# RC-ESC_2020-12-18_19-57-09.net
KiCad netlist of a schematic drawn in EasyEDA
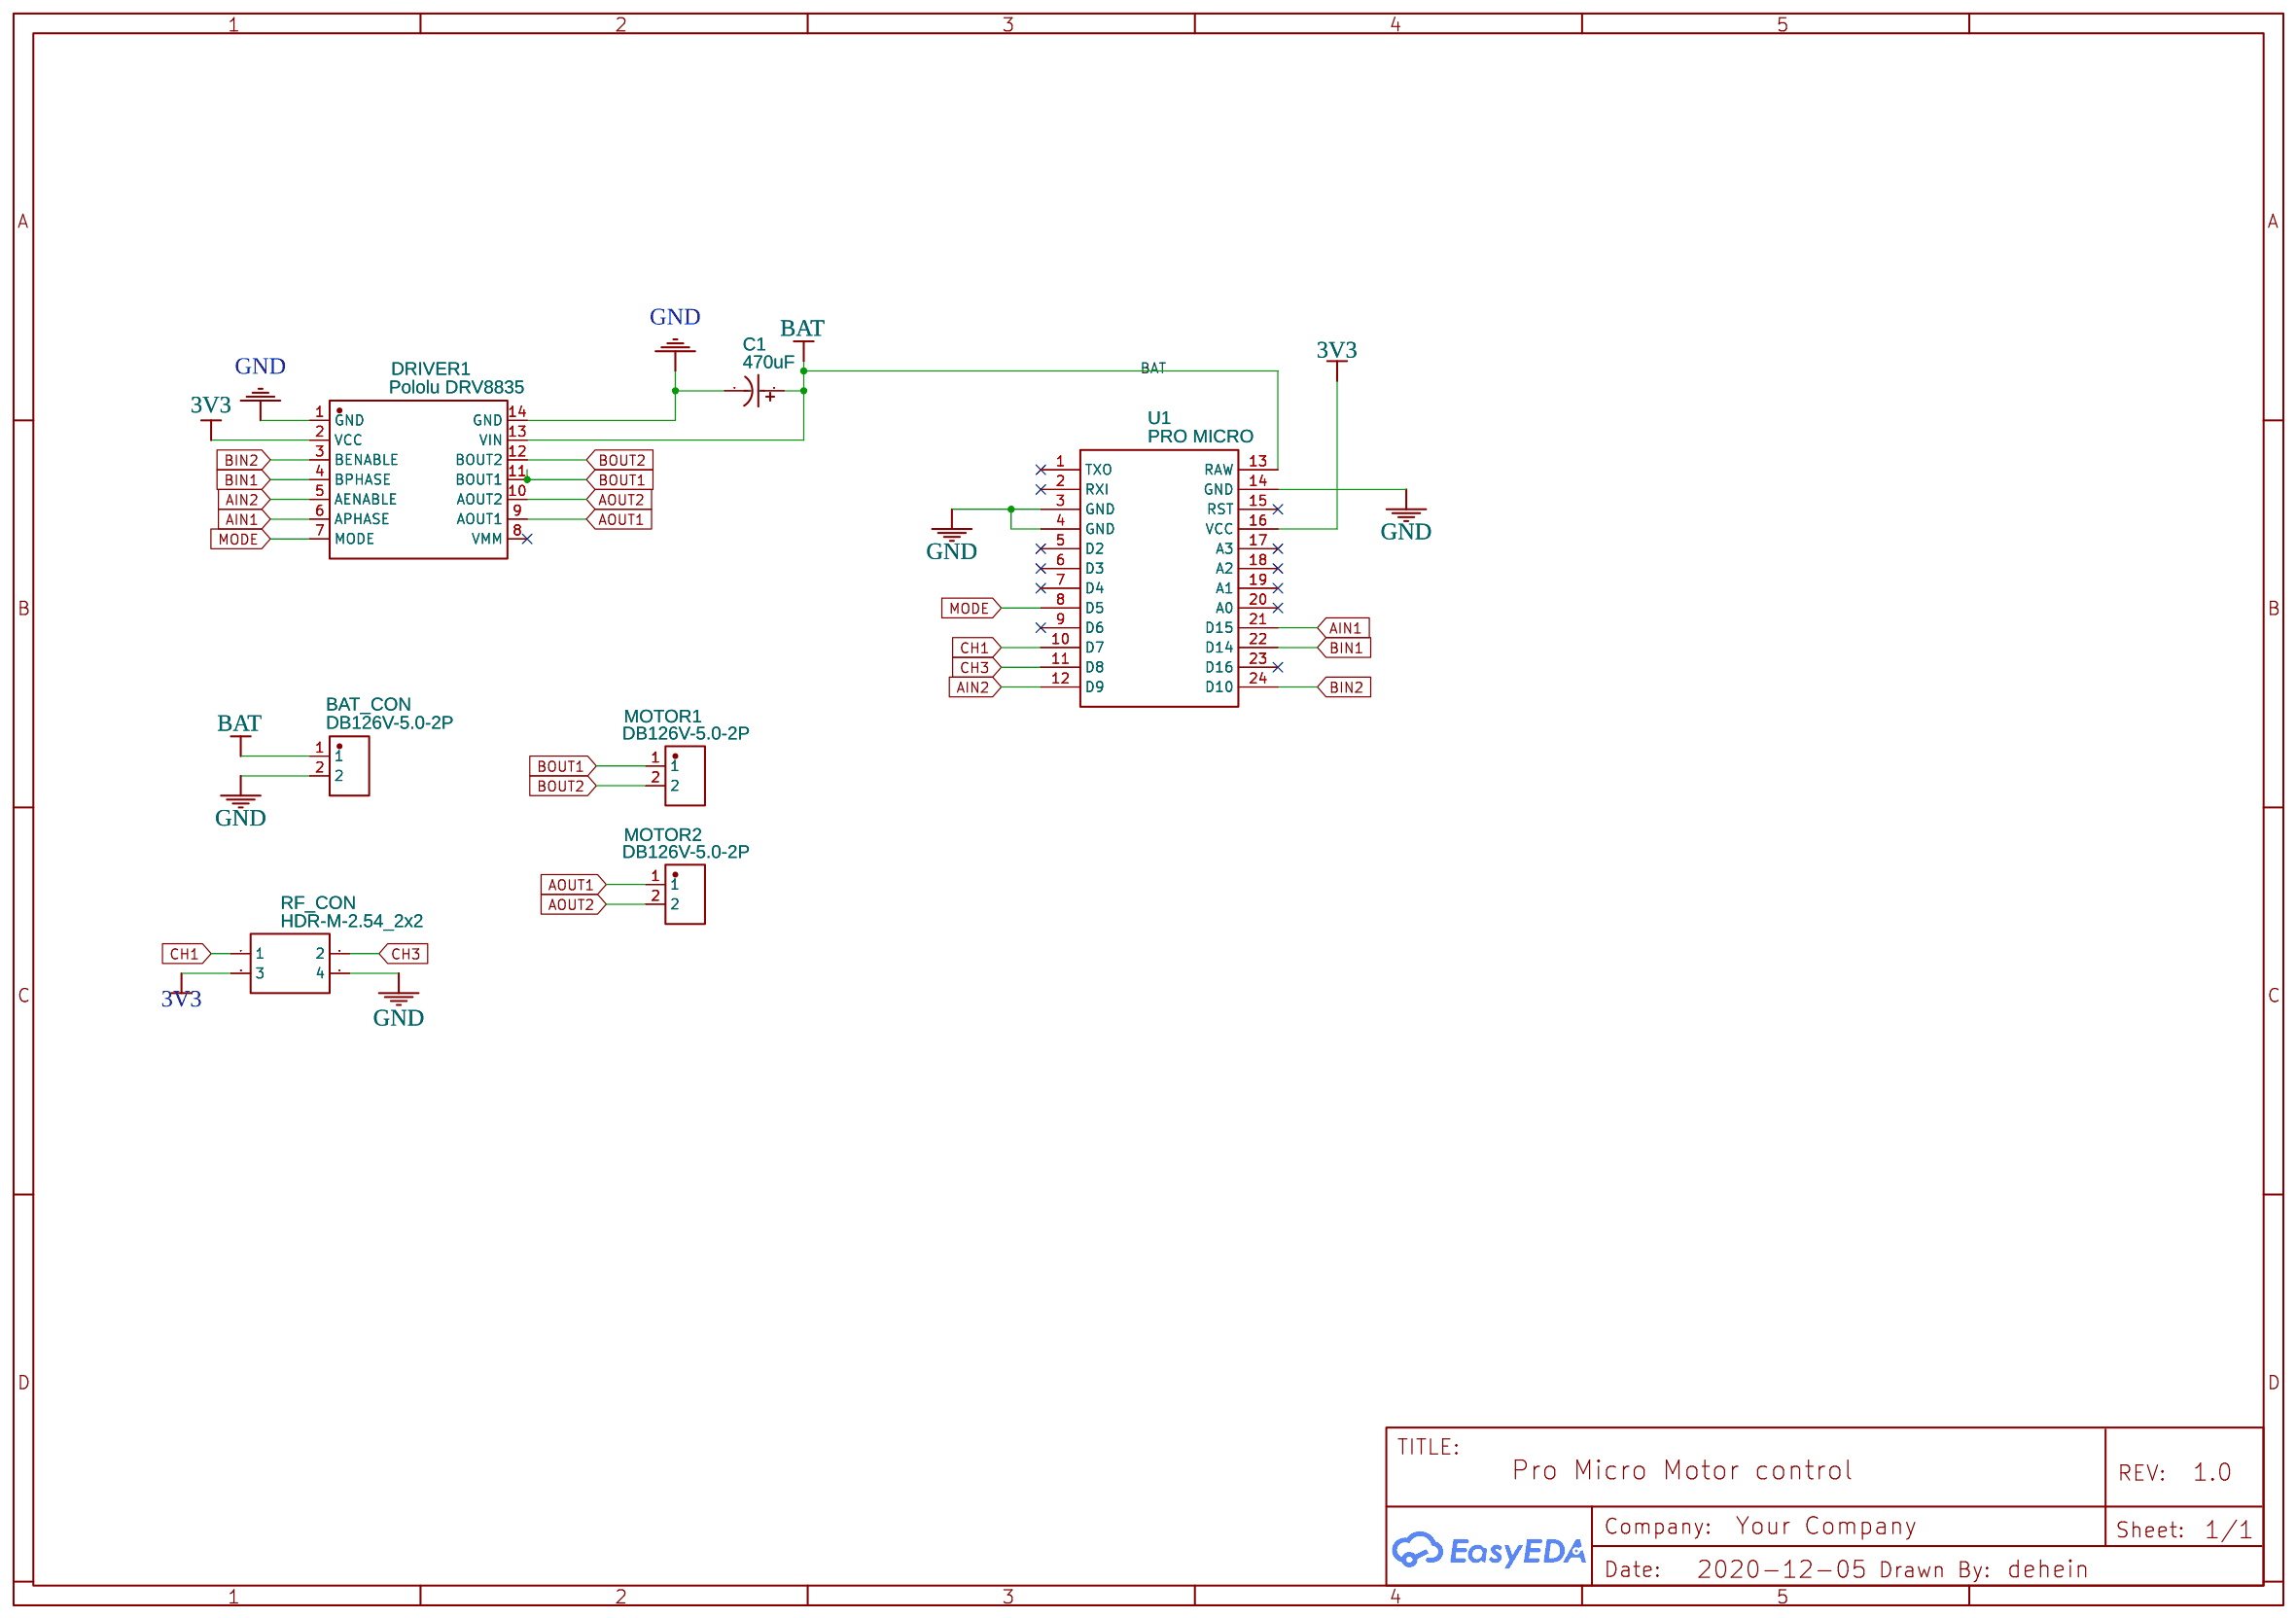
[diagram p0: schematic sheet]

(export (version "E")
  (design (tool "Eeschema 10.0.6"))
  (components
    (comp (ref "BAT_CON")
      (value "DB126V-5.0-2P")
      (fields (field (name "BOM_Supplier Part") "C395849"))
      (libsource (lib "") (part "DB126V-5.0-2P"))
    )
    (comp (ref "C1")
      (value "470uF")
      (fields
        (field (name "BOM_Manufacturer Part") "470uF 25V 8*12Black high frequency")
        (field (name "BOM_Supplier Part") "C44602")
      )
      (libsource (lib "") (part "470uF 25V 8*12Black high frequency"))
    )
    (comp (ref "DRIVER1")
      (value "Pololu DRV8835")
      (fields (field (name "BOM_Manufacturer Part") "2135"))
      (libsource (lib "") (part "Pololu DRV8835"))
    )
    (comp (ref "MOTOR1")
      (value "DB126V-5.0-2P")
      (fields (field (name "BOM_Supplier Part") "C395849"))
      (libsource (lib "") (part "DB126V-5.0-2P_1"))
    )
    (comp (ref "MOTOR2")
      (value "DB126V-5.0-2P")
      (fields (field (name "BOM_Supplier Part") "C395849"))
      (libsource (lib "") (part "DB126V-5.0-2P_1"))
    )
    (comp (ref "RF_CON")
      (value "HDR-M-2.54_2x2")
      (fields
        (field (name "BOM_Manufacturer Part") "Double Rows2.54mm2*2pHeaders  Pins")
        (field (name "BOM_Supplier Part") "C66690")
      )
      (libsource (lib "") (part "HDR-M-2.54_2x2"))
    )
    (comp (ref "U1") (value "PRO MICRO") (libsource (lib "") (part "PRO MICRO")))
  )
  (nets
    (net (code "1") (name "3V3") (class "Default")
      (node (ref "DRIVER1") (pin "2") (pinfunction "VCC_2") (pintype "unspecified"))
      (node (ref "RF_CON") (pin "3") (pinfunction "3_3") (pintype "input"))
      (node (ref "U1") (pin "16") (pinfunction "VCC_16") (pintype "unspecified"))
    )
    (net (code "2") (name "AIN1") (class "Default")
      (node (ref "DRIVER1") (pin "6") (pinfunction "APHASE_6") (pintype "unspecified"))
      (node (ref "U1") (pin "21") (pinfunction "D15_21") (pintype "unspecified"))
    )
    (net (code "3") (name "AIN2") (class "Default")
      (node (ref "DRIVER1") (pin "5") (pinfunction "AENABLE_5") (pintype "unspecified"))
      (node (ref "U1") (pin "12") (pinfunction "D9_12") (pintype "unspecified"))
    )
    (net (code "4") (name "AOUT1") (class "Default")
      (node (ref "DRIVER1") (pin "9") (pinfunction "AOUT1_9") (pintype "unspecified"))
      (node (ref "MOTOR2") (pin "1") (pinfunction "1_1") (pintype "unspecified"))
    )
    (net (code "5") (name "AOUT2") (class "Default")
      (node (ref "DRIVER1") (pin "10") (pinfunction "AOUT2_10") (pintype "unspecified"))
      (node (ref "MOTOR2") (pin "2") (pinfunction "2_2") (pintype "unspecified"))
    )
    (net (code "6") (name "BAT") (class "Default")
      (node (ref "BAT_CON") (pin "1") (pinfunction "1_1") (pintype "unspecified"))
      (node (ref "C1") (pin "1") (pinfunction "1_1") (pintype "input"))
      (node (ref "DRIVER1") (pin "13") (pinfunction "VIN_13") (pintype "unspecified"))
      (node (ref "U1") (pin "13") (pinfunction "RAW_13") (pintype "unspecified"))
    )
    (net (code "7") (name "BIN1") (class "Default")
      (node (ref "DRIVER1") (pin "4") (pinfunction "BPHASE_4") (pintype "unspecified"))
      (node (ref "U1") (pin "22") (pinfunction "D14_22") (pintype "unspecified"))
    )
    (net (code "8") (name "BIN2") (class "Default")
      (node (ref "DRIVER1") (pin "3") (pinfunction "BENABLE_3") (pintype "unspecified"))
      (node (ref "U1") (pin "24") (pinfunction "D10_24") (pintype "unspecified"))
    )
    (net (code "9") (name "BOUT1") (class "Default")
      (node (ref "DRIVER1") (pin "11") (pinfunction "BOUT1_11") (pintype "unspecified"))
      (node (ref "MOTOR1") (pin "1") (pinfunction "1_1") (pintype "unspecified"))
    )
    (net (code "10") (name "BOUT2") (class "Default")
      (node (ref "DRIVER1") (pin "12") (pinfunction "BOUT2_12") (pintype "unspecified"))
      (node (ref "MOTOR1") (pin "2") (pinfunction "2_2") (pintype "unspecified"))
    )
    (net (code "11") (name "CH1") (class "Default")
      (node (ref "RF_CON") (pin "1") (pinfunction "1_1") (pintype "input"))
      (node (ref "U1") (pin "10") (pinfunction "D7_10") (pintype "unspecified"))
    )
    (net (code "12") (name "CH3") (class "Default")
      (node (ref "RF_CON") (pin "2") (pinfunction "2_2") (pintype "input"))
      (node (ref "U1") (pin "11") (pinfunction "D8_11") (pintype "unspecified"))
    )
    (net (code "13") (name "GND") (class "Default")
      (node (ref "BAT_CON") (pin "2") (pinfunction "2_2") (pintype "unspecified"))
      (node (ref "C1") (pin "2") (pinfunction "2_2") (pintype "input"))
      (node (ref "DRIVER1") (pin "1") (pinfunction "GND_1") (pintype "unspecified"))
      (node (ref "DRIVER1") (pin "14") (pinfunction "GND_14") (pintype "unspecified"))
      (node (ref "RF_CON") (pin "4") (pinfunction "4_4") (pintype "input"))
      (node (ref "U1") (pin "14") (pinfunction "GND_14") (pintype "unspecified"))
      (node (ref "U1") (pin "3") (pinfunction "GND_3") (pintype "unspecified"))
      (node (ref "U1") (pin "4") (pinfunction "GND_4") (pintype "unspecified"))
    )
    (net (code "14") (name "MODE") (class "Default")
      (node (ref "DRIVER1") (pin "7") (pinfunction "MODE_7") (pintype "unspecified"))
      (node (ref "U1") (pin "8") (pinfunction "D5_8") (pintype "unspecified"))
    )
    (net (code "15") (name "unconnected-(DRIVER1-VMM-Pad8)") (class "Default")
      (node (ref "DRIVER1") (pin "8") (pinfunction "VMM_8") (pintype "unspecified+no_connect"))
    )
    (net (code "16") (name "unconnected-(U1-A0-Pad20)") (class "Default")
      (node (ref "U1") (pin "20") (pinfunction "A0_20") (pintype "unspecified+no_connect"))
    )
    (net (code "17") (name "unconnected-(U1-A1-Pad19)") (class "Default")
      (node (ref "U1") (pin "19") (pinfunction "A1_19") (pintype "unspecified+no_connect"))
    )
    (net (code "18") (name "unconnected-(U1-A2-Pad18)") (class "Default")
      (node (ref "U1") (pin "18") (pinfunction "A2_18") (pintype "unspecified+no_connect"))
    )
    (net (code "19") (name "unconnected-(U1-A3-Pad17)") (class "Default")
      (node (ref "U1") (pin "17") (pinfunction "A3_17") (pintype "unspecified+no_connect"))
    )
    (net (code "20") (name "unconnected-(U1-D2-Pad5)") (class "Default")
      (node (ref "U1") (pin "5") (pinfunction "D2_5") (pintype "unspecified+no_connect"))
    )
    (net (code "21") (name "unconnected-(U1-D3-Pad6)") (class "Default")
      (node (ref "U1") (pin "6") (pinfunction "D3_6") (pintype "unspecified+no_connect"))
    )
    (net (code "22") (name "unconnected-(U1-D4-Pad7)") (class "Default")
      (node (ref "U1") (pin "7") (pinfunction "D4_7") (pintype "unspecified+no_connect"))
    )
    (net (code "23") (name "unconnected-(U1-D6-Pad9)") (class "Default")
      (node (ref "U1") (pin "9") (pinfunction "D6_9") (pintype "unspecified+no_connect"))
    )
    (net (code "24") (name "unconnected-(U1-D16-Pad23)") (class "Default")
      (node (ref "U1") (pin "23") (pinfunction "D16_23") (pintype "unspecified+no_connect"))
    )
    (net (code "25") (name "unconnected-(U1-RST-Pad15)") (class "Default")
      (node (ref "U1") (pin "15") (pinfunction "RST_15") (pintype "unspecified+no_connect"))
    )
    (net (code "26") (name "unconnected-(U1-RXI-Pad2)") (class "Default")
      (node (ref "U1") (pin "2") (pinfunction "RXI_2") (pintype "unspecified+no_connect"))
    )
    (net (code "27") (name "unconnected-(U1-TXO-Pad1)") (class "Default")
      (node (ref "U1") (pin "1") (pinfunction "TXO_1") (pintype "unspecified+no_connect"))
    )
  )
)
